# 12VInputProtection.net
KiCad netlist of a schematic drawn in Altium Designer
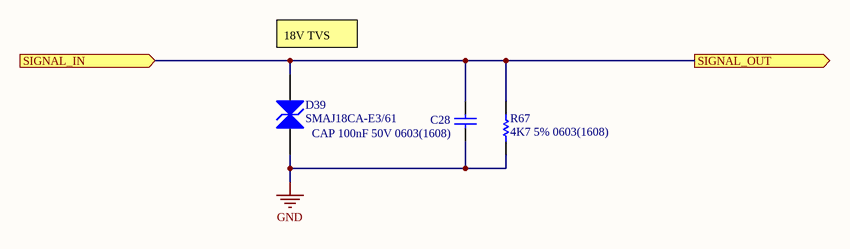
[diagram p0: 12VInputProtection.SchDoc]

(export (version "E")
  (design (tool "Eeschema 10.0.6"))
  (components
    (comp (ref "C28")
      (value "CAP 100nF 50V 0603(1608)")
      (footprint "CAPC0603(1608)100_L")
      (description "CAP 100nF 50V ±5% 0603 (1608 Metric) Thickness 1mm SMD")
      (fields (field (name "TOLERANCE") "Â±5%"))
      (libsource (lib "Altium Content Vault") (part "CAP"))
    )
    (comp (ref "D39")
      (value "SMAJ18CA-E3/61")
      (footprint "VISH-DO-214AC-2_M")
      (fields (field (name "MANUFACTURER") "Vishay Semiconductor"))
      (libsource (lib "Altium Content Vault") (part "VISH-A1A2-2"))
    )
    (comp (ref "R67")
      (value "4K7 5% 0603(1608)")
      (footprint "RESC0603(1608)_N")
      (description "4K7 0.1W 5% 0603 (1608 Metric)  SMD")
      (fields (field (name "TOLERANCE") "5 %") (field (name "POWER") "0.1 W"))
      (libsource (lib "Altium Content Vault") (part "RES"))
    )
  )
  (nets
    (net (code "1") (name "/SIGNAL_IN") (class "Default")
      (node (ref "C28") (pin "1") (pinfunction "1_1") (pintype "passive"))
      (node (ref "D39") (pin "2") (pinfunction "A2_2") (pintype "passive"))
      (node (ref "R67") (pin "2") (pinfunction "2_2") (pintype "passive"))
    )
    (net (code "2") (name "GND") (class "Default")
      (node (ref "C28") (pin "2") (pinfunction "2_2") (pintype "passive"))
      (node (ref "D39") (pin "1") (pinfunction "A1_1") (pintype "passive"))
      (node (ref "R67") (pin "1") (pinfunction "1_1") (pintype "passive"))
    )
  )
)
